# Full_Design.net
KiCad netlist of a schematic drawn in Altium Designer
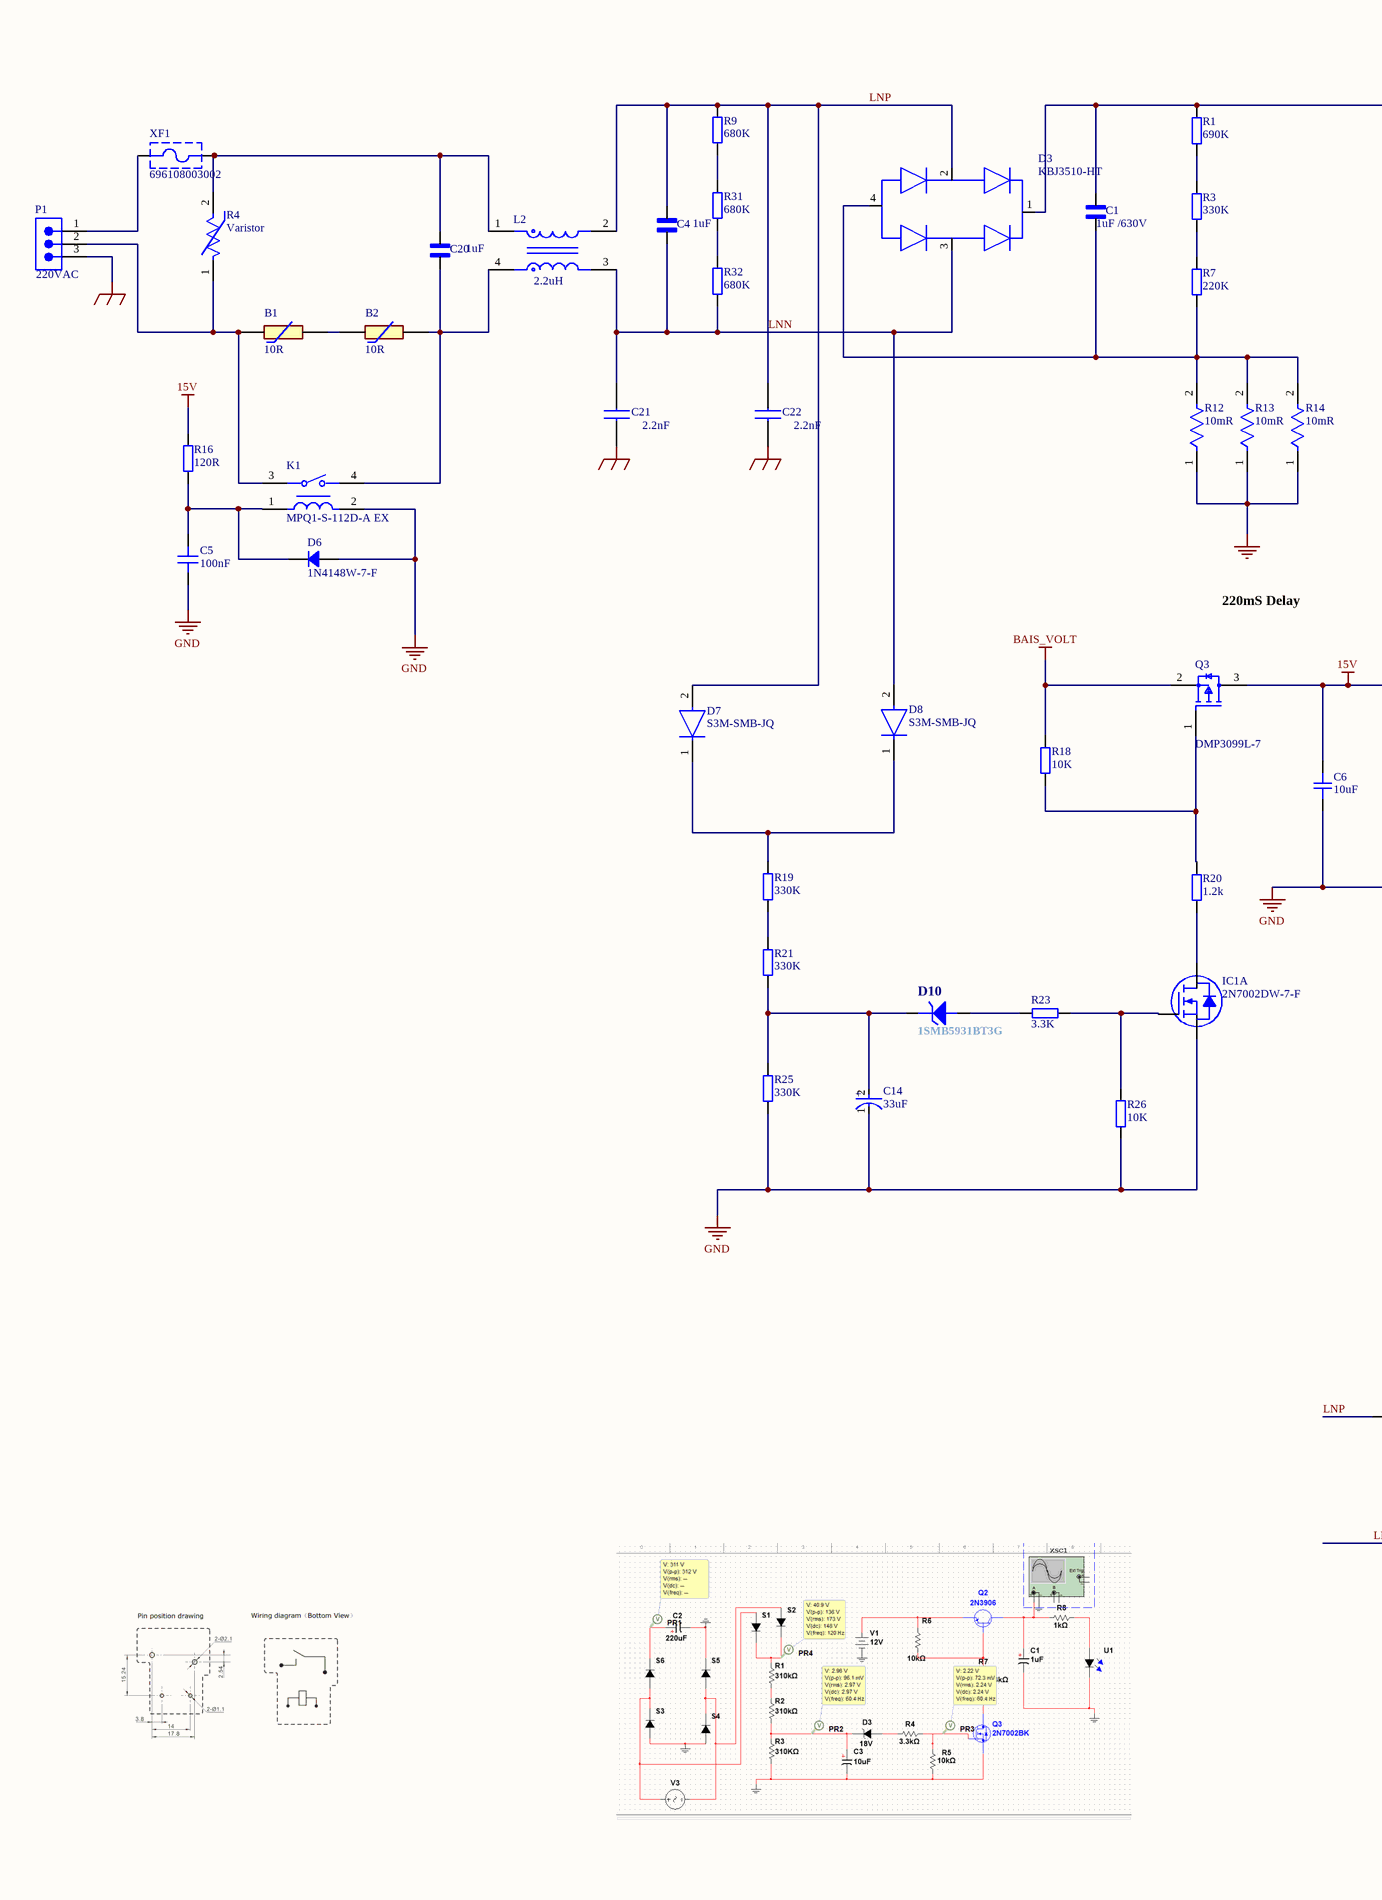
[diagram p0: Full Design.SchDoc, left]
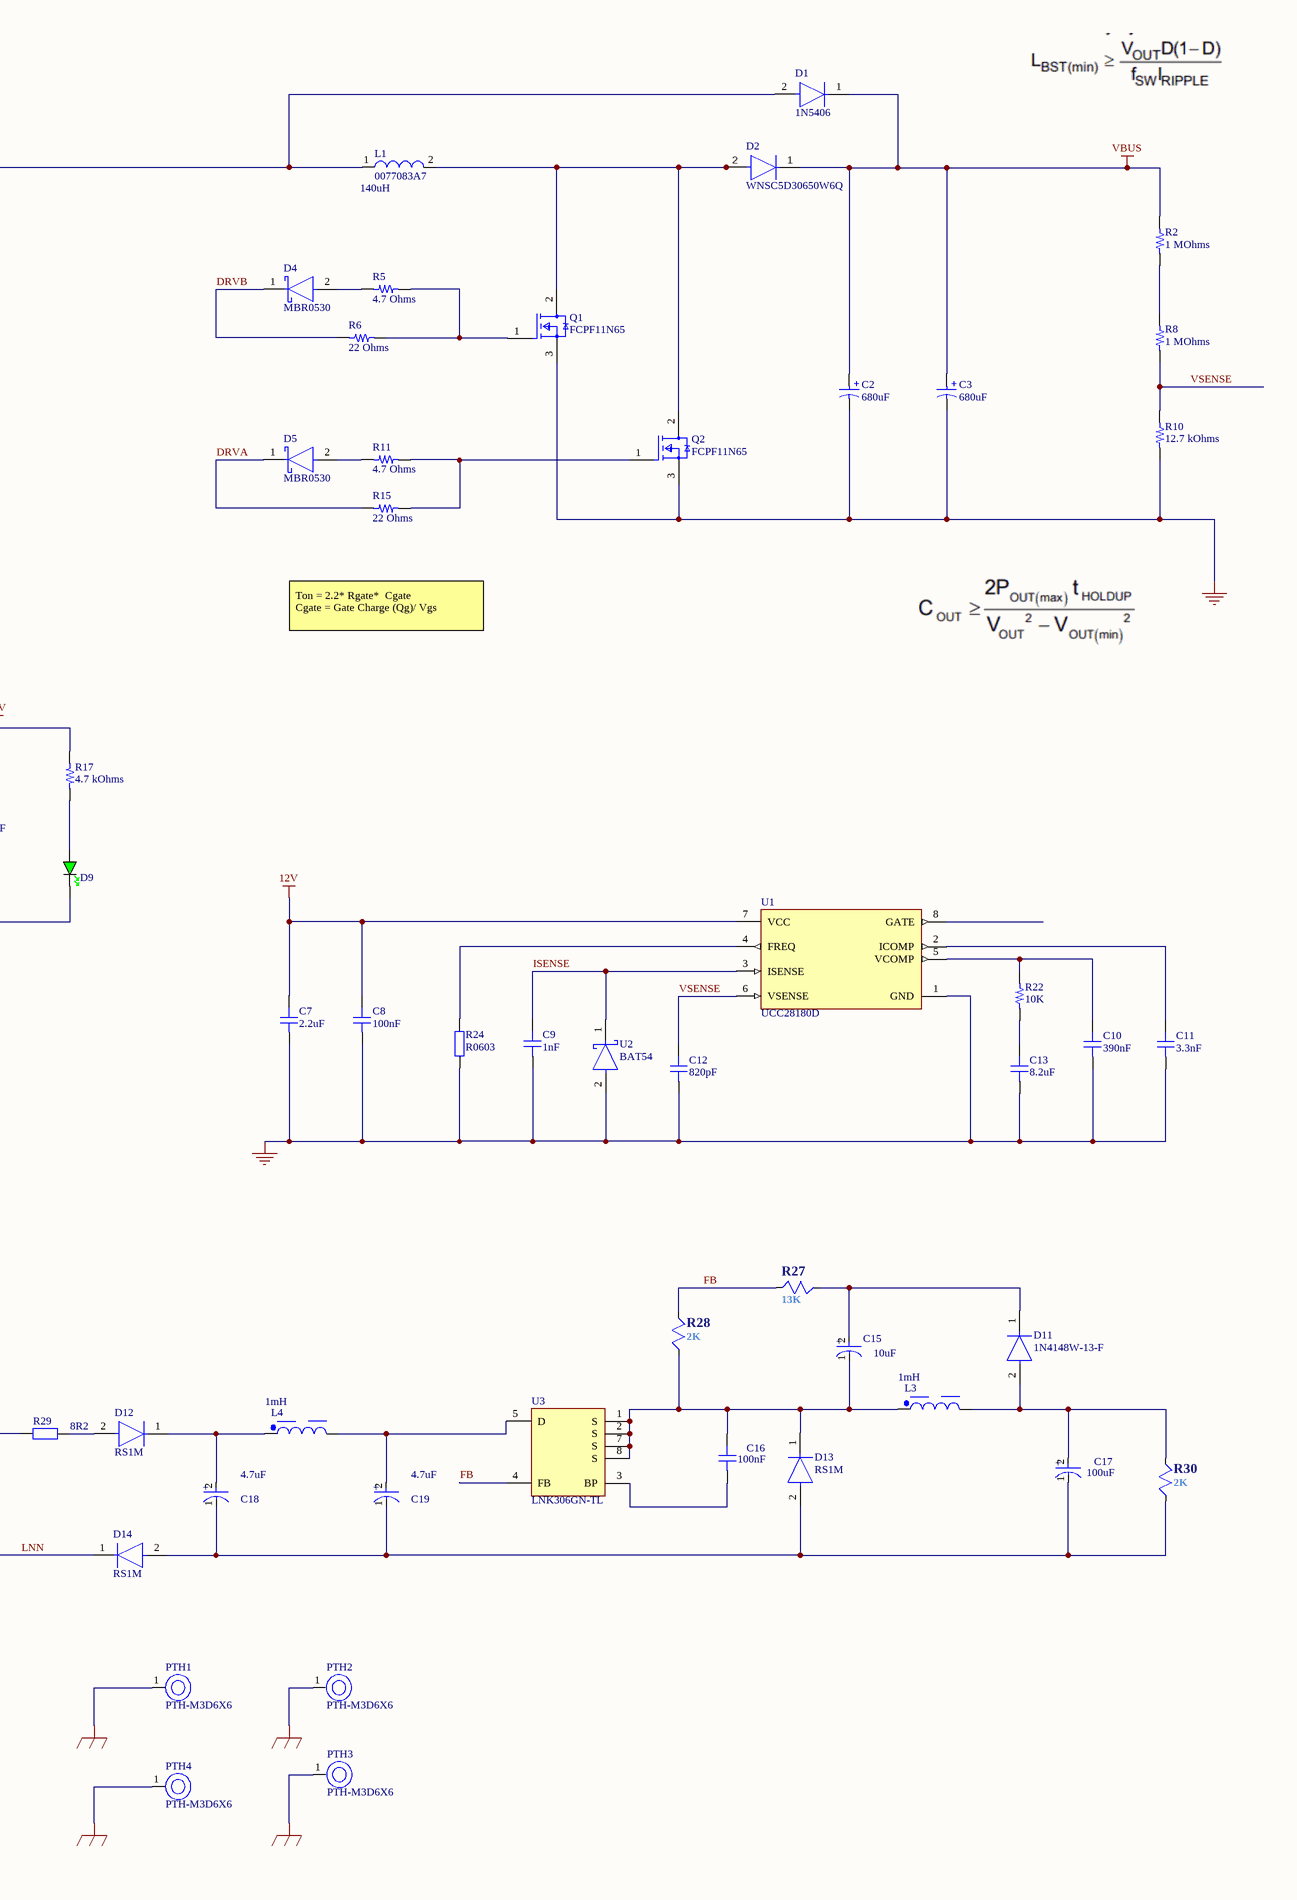
[diagram p1: Full Design.SchDoc, right]

(export (version "E")
  (design (tool "Eeschema 10.0.6"))
  (components
    (comp (ref "B1")
      (value "10R")
      (footprint "B57237S0100M051")
      (description "NTC Inrush Current Limiters, Resistance (at 25)=10, Maximum Current=3.7A")
      (fields
        (field (name "MOUSER PART NUMBER") "871-B57237S0100M051")
        (field (name "MANUFACTURER_PART_NUMBER") "B57237S0100M051")
      )
      (libsource (lib "Görev Yükü's Libary") (part "B57237S0100M051"))
    )
    (comp (ref "B2")
      (value "10R")
      (footprint "B57237S0100M051")
      (description "NTC Inrush Current Limiters, Resistance (at 25)=10, Maximum Current=3.7A")
      (fields
        (field (name "MOUSER PART NUMBER") "871-B57237S0100M051")
        (field (name "MANUFACTURER_PART_NUMBER") "B57237S0100M051")
      )
      (libsource (lib "Görev Yükü's Libary") (part "B57237S0100M051"))
    )
    (comp (ref "C1")
      (value "1uF /630V")
      (footprint "CAPRR2750W80L3150T1100H1900")
      (description "CAP FILM 1UF 10% 630VDC RADIAL")
      (fields (field (name "MF") "EPCOS - TDK Electronics") (field (name "MP") "B32924C3105K000"))
      (libsource (lib "Görev Yükü's Libary") (part "CAP_B32924C3105K189"))
    )
    (comp (ref "C2")
      (value "680uF")
      (footprint "WCAP-AI3H_D35H55")
      (description "CAP.EL.680uF ±20%  450V 2.2A 5000 Hrs @ 105°C")
      (fields (field (name "TOLERANCE") "20%"))
      (libsource (lib "Altium Content Vault") (part "Capacitor_Polarized"))
    )
    (comp (ref "C3")
      (value "680uF")
      (footprint "WCAP-AI3H_D35H55")
      (description "CAP.EL.680uF ±20%  450V 2.2A 5000 Hrs @ 105°C")
      (fields (field (name "TOLERANCE") "20%"))
      (libsource (lib "Altium Content Vault") (part "Capacitor_Polarized"))
    )
    (comp (ref "C4")
      (value "1uF")
      (footprint "CAPRR2750W80L3150T1100H1900")
      (description "CAP FILM 1UF 10% 630VDC RADIAL")
      (fields
        (field (name "MF") "{'manufacturer': u'EPCOS - TDK Electronics'}")
        (field (name "MP") "B32924C3105K000")
      )
      (libsource (lib "Görev Yükü's Libary") (part "CAP_B32924C3105K189"))
    )
    (comp (ref "C5")
      (value "100nF")
      (footprint "CAP 0603_1608")
      (description "CAP CER 1UF 16V X7R 0603")
      (fields (field (name "PART NUMBER") "C0603C105K4RACAUTO") (field (name "MANUFACTURER") "KEMET"))
      (libsource (lib "Celestial Altium Library - altium_library") (part "Capacitor"))
    )
    (comp (ref "C6")
      (value "10uF")
      (footprint "CAP_0805")
      (description "Capacitor SMD 0805")
      (libsource (lib "Phil-lab") (part "CAP_0805"))
    )
    (comp (ref "C7")
      (value "2.2uF")
      (footprint "CAP_0805")
      (description "2.2uF 50V")
      (libsource (lib "Phil-lab") (part "CAP_0805"))
    )
    (comp (ref "C8")
      (value "100nF")
      (footprint "CAP_0805")
      (description "Capacitor SMD 0805")
      (libsource (lib "Phil-lab") (part "CAP_0805"))
    )
    (comp (ref "C9")
      (value "1nF")
      (footprint "CAP_0805")
      (description "Capacitor SMD 0805")
      (libsource (lib "Phil-lab") (part "CAP_0805"))
    )
    (comp (ref "C10")
      (value "390nF")
      (footprint "CAP_0805")
      (description "Capacitor SMD 0805")
      (libsource (lib "Phil-lab") (part "CAP_0805"))
    )
    (comp (ref "C11")
      (value "3.3nF")
      (footprint "CAP_0805")
      (description "Capacitor SMD 0805")
      (libsource (lib "Phil-lab") (part "CAP_0805"))
    )
    (comp (ref "C12")
      (value "820pF")
      (footprint "CAP_0805")
      (description "Capacitor SMD 0805")
      (libsource (lib "Phil-lab") (part "CAP_0805"))
    )
    (comp (ref "C13")
      (value "8.2uF")
      (footprint "CAP_0805")
      (description "Capacitor SMD 0805")
      (libsource (lib "Phil-lab") (part "CAP_0805"))
    )
    (comp (ref "C14")
      (value "33uF")
      (footprint "FP-FKE-MFG")
      (fields (field (name "VOLTAGE") "50V") (field (name "TOLERANCE") "20%"))
      (libsource (lib "Altium Content Vault") (part "203bc49f2ac43e59fd269a8c329ed05"))
    )
    (comp (ref "C15")
      (value "SC1V106M05005VR")
      (footprint "FP-FKC-MFG")
      (description "CAP.EL.10uF 35V 5x5.3 85C SMD SAMWHA")
      (fields
        (field (name "TOLERANCE") "20%")
        (field (name "VOLTAGE") "35V")
        (field (name "CAPACITANCE") "10uF")
      )
      (libsource (lib "Altium Content Vault") (part "a00bbbee19879c290e62620ae7e47b1"))
    )
    (comp (ref "C16")
      (value "C1210C104KCRACTU")
      (footprint "CAP_1210")
      (description "Capacitor SMD 1210")
      (fields (field (name "MANUFACTURER") "KEMET") (field (name "CAPACITANCE") "100nF"))
      (libsource (lib "Phil-lab") (part "CAP_1210"))
    )
    (comp (ref "C17")
      (value "CKL025M101F10PKKKV00A")
      (footprint "FP-SEV8X10_5-MFG")
      (description "CAP.EL.100uF 25V 8x10 105C 5000H AEC-Q200 SMT")
      (fields (field (name "CAPACITANCE") "100uF") (field (name "TOLERANCE") "20%"))
      (libsource (lib "Altium Content Vault") (part "203bc49f2ac43e59fd269a8c329ed05"))
    )
    (comp (ref "C18")
      (value "PKLH-400V4R7MG125-T/A5.0")
      (footprint "FP-RAD-TH-D_10_0_5-L_12_5-MFG")
      (description "CAP.EL.4u7 400V 10X12.5 5MM %20 105C LOW IMP")
      (fields (field (name "TOLERANCE") "20%") (field (name "CAPACITANCE") "4.7uF"))
      (libsource (lib "Altium Content Vault") (part "203bc49f2ac43e59fd269a8c329ed05"))
    )
    (comp (ref "C19")
      (value "PKLH-400V4R7MG125-T/A5.0")
      (footprint "FP-RAD-TH-D_10_0_5-L_12_5-MFG")
      (description "CAP.EL.4u7 400V 10X12.5 5MM %20 105C LOW IMP")
      (fields (field (name "TOLERANCE") "20%") (field (name "CAPACITANCE") "4.7uF"))
      (libsource (lib "Altium Content Vault") (part "203bc49f2ac43e59fd269a8c329ed05"))
    )
    (comp (ref "C20")
      (value "1uF")
      (footprint "CAPRR2750W80L3150T1100H1900")
      (description "CAP FILM 1UF 10% 630VDC RADIAL")
      (fields
        (field (name "MF") "{'manufacturer': u'EPCOS - TDK Electronics'}")
        (field (name "MP") "B32924C3105K000")
      )
      (libsource (lib "Görev Yükü's Libary") (part "CAP_B32924C3105K189"))
    )
    (comp (ref "C21")
      (value "2.2nF")
      (footprint "WYO222MCMBRAKR")
      (description "2200 pF +/-20% 440VAC Ceramic Capacitor Y5U (E) Radial, Disc")
      (fields
        (field (name "MANUFACTURER_PART_NUMBER") "WYO222MCMBRAKR")
        (field (name "MOUSER PART NUMBER") "75-WYO222MCMBRAKR")
      )
      (libsource (lib "Görev Yükü's Libary") (part "WYO222MCMBRAKR"))
    )
    (comp (ref "C22")
      (value "2.2nF")
      (footprint "WYO222MCMBRAKR")
      (description "2200 pF +/-20% 440VAC Ceramic Capacitor Y5U (E) Radial, Disc")
      (fields
        (field (name "MANUFACTURER_PART_NUMBER") "WYO222MCMBRAKR")
        (field (name "MOUSER PART NUMBER") "75-WYO222MCMBRAKR")
      )
      (libsource (lib "Görev Yükü's Libary") (part "WYO222MCMBRAKR"))
    )
    (comp (ref "D1")
      (value "1N5406")
      (footprint "FP-1N5406-E3-54-MFG")
      (description "DIODE GEN PURP 600V 3A DO201AD")
      (libsource (lib "Altium Content Vault") (part "d7152d700b627762746794eb795d46e"))
    )
    (comp (ref "D2")
      (value "WNSC5D30650W6Q")
      (footprint "Diode")
      (description "DIODE SIL.CARB.SCHOTTKY 30A 650V TO247F-2L THT")
      (libsource (lib "Görev Yükü's Libary") (part "Diode,"))
    )
    (comp (ref "D3")
      (value "KBJ3510-HT")
      (footprint "DIOB_GBJ2510-F")
      (description "DIODE BRIDGE 35A 1000V 1PH KBJ THT")
      (libsource (lib "Görev Yükü's Libary") (part "KBJ3510-HT"))
    )
    (comp (ref "D4")
      (value "MBR0530")
      (footprint "FP-425-04-MFG")
      (description "DIODE SCHOTTKY 30V 500MA SOD123")
      (libsource (lib "Altium Content Vault") (part "1d6ec82d83fb6aee721767c19dac4b9"))
    )
    (comp (ref "D5")
      (value "MBR0530")
      (footprint "FP-425-04-MFG")
      (description "DIODE SCHOTTKY 30V 500MA SOD123")
      (libsource (lib "Altium Content Vault") (part "1d6ec82d83fb6aee721767c19dac4b9"))
    )
    (comp (ref "D6")
      (value "1N4148W-7-F")
      (footprint "SOD-123")
      (description "DIODE GEN PURP 100V 300MA SOD123")
      (fields (field (name "MANUFACTURER") "Diodes Incorporated"))
      (libsource (lib "Celestial Altium Library - altium_library") (part "Diode"))
    )
    (comp (ref "D7")
      (value "S3M-SMB-JQ")
      (footprint "FP-95401-MFG")
      (description "DIODE STAND. Single 3A 1000V SMT DO214AA")
      (libsource (lib "Altium Content Vault") (part "d7152d700b627762746794eb795d46e"))
    )
    (comp (ref "D8")
      (value "S3M-SMB-JQ")
      (footprint "FP-95401-MFG")
      (description "-DIODE STAND. Single 3A 1000V SMT DO214AA")
      (libsource (lib "Altium Content Vault") (part "d7152d700b627762746794eb795d46e"))
    )
    (comp (ref "D9")
      (value "GREEN")
      (footprint "LED_0603_GREEN")
      (description "LED 0603 GREEN SMD")
      (libsource (lib "Phil-lab") (part "LED_0603_GREEN"))
    )
    (comp (ref "D10")
      (value "1SMB5931BT3G")
      (footprint "SMB")
      (description "DIODE ZENER 3W 18V ±5% DO214AA (SMB) SMT")
      (libsource (lib "WG_MainBoard_NV1") (part "ZENER-1_1"))
    )
    (comp (ref "D11")
      (value "1N4148W-13-F")
      (footprint "FP-SOD123-MFG")
      (description "DIODE GEN PURP 100V 150MA SOD123")
      (fields
        (field (name "OCTOPART") "https://octopart.com/1n4148w-13-f-diodes+inc.-2359612")
        (field (name "MANUFACTURER") "Diodes Inc.")
      )
      (libsource (lib "Altium Content Vault") (part "d7152d700b627762746794eb795d46e"))
    )
    (comp (ref "D12")
      (value "RS1M")
      (footprint "FP-403AE-MFG")
      (description "DIODE GEN PURP 1KV 1A SMA")
      (fields
        (field (name "OCTOPART") "https://octopart.com/rs1m-on+semiconductor-84331238")
        (field (name "MANUFACTURER") "ON Semiconductor")
      )
      (libsource (lib "Altium Content Vault") (part "d7152d700b627762746794eb795d46e"))
    )
    (comp (ref "D13")
      (value "RS1M")
      (footprint "FP-403AE-MFG")
      (description "DIODE GEN PURP 1KV 1A SMA")
      (fields
        (field (name "OCTOPART") "https://octopart.com/rs1m-on+semiconductor-84331238")
        (field (name "MANUFACTURER") "ON Semiconductor")
      )
      (libsource (lib "Altium Content Vault") (part "d7152d700b627762746794eb795d46e"))
    )
    (comp (ref "D14")
      (value "RS1M")
      (footprint "FP-403AE-MFG")
      (description "DIODE GEN PURP 1KV 1A SMA")
      (fields
        (field (name "OCTOPART") "https://octopart.com/rs1m-on+semiconductor-84331238")
        (field (name "MANUFACTURER") "ON Semiconductor")
      )
      (libsource (lib "Altium Content Vault") (part "d7152d700b627762746794eb795d46e"))
    )
    (comp (ref "IC1")
      (value "2N7002DW-7-F")
      (footprint "DIODES SOT-363")
      (description "MOSFET 2N-CH 60V 0.23A SOT-363")
      (fields (field (name "MANUFACTURER") "Diodes Incorporated"))
      (libsource (lib "Celestial Altium Library - altium_library") (part "INFINEON DUAL MOSFET N-CH SOT363"))
    )
    (comp (ref "K1")
      (value "MPQ1-S-112D-A EX")
      (footprint "MPQ1-S-112D-A EX")
      (description "RELAY POWER 30A 12VDC FormA PCB EXPLOSION PROOF")
      (libsource (lib "Schematics") (part "RELAY_MPQ1-S-112D-A EX"))
    )
    (comp (ref "L1")
      (value "0077083A7")
      (footprint "0077083A7")
      (fields (field (name "INDUCTANCE") "140uH"))
      (libsource (lib "Görev Yükü's Libary") (part "0077083A7"))
    )
    (comp (ref "L2")
      (value "2.2uH")
      (footprint "FP-PLA10A-PLH10A-MFG")
      (description "Common Mode Choke Dual 20mH 0.5A 1.8Ω DCR Thru-Hole Bulk")
      (libsource (lib "Altium Content Vault") (part "48057101139d7a9ca9ebeb60f9e3dee"))
    )
    (comp (ref "L3")
      (value "FPI0705-102K(W0.15)")
      (footprint "WE-PD2_1054")
      (description "INDUCTOR POWER 1mH 7.8X7.0X5.0MM SMD")
      (fields (field (name "TOLERANCE") "10%") (field (name "INDUCTANCE") "1mH"))
      (libsource (lib "Altium Content Vault") (part "Inductor - 2"))
    )
    (comp (ref "L4")
      (value "FPI0705-102K(W0.15)")
      (footprint "WE-PD2_1054")
      (description "INDUCTOR POWER 1mH 7.8X7.0X5.0MM SMD")
      (fields (field (name "TOLERANCE") "10%") (field (name "INDUCTANCE") "1mH"))
      (libsource (lib "Altium Content Vault") (part "Inductor - 2"))
    )
    (comp (ref "P1")
      (value "220VAC")
      (footprint "691311700003")
      (fields (field (name "VOLTAGE") "300V"))
      (libsource (lib "Altium Content Vault") (part "TBL - 1R - 03P - Male"))
    )
    (comp (ref "PTH1")
      (value "PTH-M3D6X6")
      (footprint "PH3.2")
      (libsource (lib "Components") (part "PTH_S1"))
    )
    (comp (ref "PTH2")
      (value "PTH-M3D6X6")
      (footprint "PH3.2")
      (libsource (lib "Components") (part "PTH_S1"))
    )
    (comp (ref "PTH3")
      (value "PTH-M3D6X6")
      (footprint "PH3.2")
      (libsource (lib "Components") (part "PTH_S1"))
    )
    (comp (ref "PTH4")
      (value "PTH-M3D6X6")
      (footprint "PH3.2")
      (libsource (lib "Components") (part "PTH_S1"))
    )
    (comp (ref "Q1")
      (value "FCPF11N65")
      (footprint "FP-TO-220F-MFG")
      (description "FCPF11N65 Res Thick Film 1210 13.7 Ohm 1% 1/2W 100ppm/C Molded SMD Embossed Carrier T/R")
      (libsource (lib "Altium Content Vault") (part "277670f45256a45703965f138927d09"))
    )
    (comp (ref "Q2")
      (value "FCPF11N65")
      (footprint "FP-TO-220F-MFG")
      (description "FCPF11N65 Res Thick Film 1210 13.7 Ohm 1% 1/2W 100ppm/C Molded SMD Embossed Carrier T/R")
      (libsource (lib "Altium Content Vault") (part "277670f45256a45703965f138927d09"))
    )
    (comp (ref "Q3")
      (value "DMP3099L-7")
      (footprint "FP-SOT23-IPC_B")
      (description "MOSFET P-CH 30V SOT23")
      (libsource (lib "Altium Content Vault") (part "d876440acba04c58a9f817a20952145"))
    )
    (comp (ref "R1")
      (value "690K")
      (footprint "RES_0603")
      (description "Resistor SMD 0603")
      (libsource (lib "Phil-lab") (part "RES_0603"))
    )
    (comp (ref "R2")
      (value "1 MOhms")
      (footprint "YAGEO RES 0402_1005")
      (description "RES 1 MOHM 1% 1/16W 0402")
      (fields (field (name "PART NUMBER") "AC0402FR-131ML") (field (name "MANUFACTURER") "Yageo"))
      (libsource (lib "Celestial Altium Library - altium_library") (part "Resistor"))
    )
    (comp (ref "R3")
      (value "330K")
      (footprint "RES_0603")
      (description "Resistor SMD 0603")
      (libsource (lib "Phil-lab") (part "RES_0603"))
    )
    (comp (ref "R4")
      (value "Varistor")
      (footprint "FP-B72214S0301K101-0")
      (description "VARISTOR 470V 4.5KA DISC 14MM")
      (fields (field (name "TOLERANCE") "10%"))
      (libsource (lib "Altium Content Vault") (part "78a88060d5b7b043d6e48adc4284376"))
    )
    (comp (ref "R5")
      (value "4.7 Ohms")
      (footprint "RES 0603_1608")
      (description "RES SMD 4.7 OHM 5% 1/10W 0603")
      (fields (field (name "PART NUMBER") "CR0603-J/-4R7ELF") (field (name "MANUFACTURER") "Bourns Inc."))
      (libsource (lib "Celestial Altium Library - altium_library") (part "Resistor"))
    )
    (comp (ref "R6")
      (value "22 Ohms")
      (footprint "RES 0603_1608")
      (description "RES SMD 22 OHM 5% 1/10W 0603")
      (fields (field (name "PART NUMBER") "CR0603-JW-220ELF") (field (name "MANUFACTURER") "Bourns Inc."))
      (libsource (lib "Celestial Altium Library - altium_library") (part "Resistor"))
    )
    (comp (ref "R7")
      (value "220K")
      (footprint "RES_0603")
      (description "Resistor SMD 0603")
      (libsource (lib "Phil-lab") (part "RES_0603"))
    )
    (comp (ref "R8")
      (value "1 MOhms")
      (footprint "YAGEO RES 0402_1005")
      (description "RES 1 MOHM 1% 1/16W 0402")
      (fields (field (name "PART NUMBER") "AC0402FR-131ML") (field (name "MANUFACTURER") "Yageo"))
      (libsource (lib "Celestial Altium Library - altium_library") (part "Resistor"))
    )
    (comp (ref "R9")
      (value "680K")
      (footprint "RES_0603")
      (description "Resistor SMD 0603")
      (libsource (lib "Phil-lab") (part "RES_0603"))
    )
    (comp (ref "R10")
      (value "12.7 kOhms")
      (footprint "RES 0402_1005")
      (description "RES 12.7K OHM 1% 1/16W 0402")
      (fields
        (field (name "PART NUMBER") "RMCF0402FT12K7")
        (field (name "MANUFACTURER") "Stackpole Electronics Inc")
      )
      (libsource (lib "Celestial Altium Library - altium_library") (part "Resistor"))
    )
    (comp (ref "R11")
      (value "4.7 Ohms")
      (footprint "RES 0603_1608")
      (description "RES SMD 4.7 OHM 5% 1/10W 0603")
      (fields (field (name "PART NUMBER") "CR0603-J/-4R7ELF") (field (name "MANUFACTURER") "Bourns Inc."))
      (libsource (lib "Celestial Altium Library - altium_library") (part "Resistor"))
    )
    (comp (ref "R12")
      (value "10mR")
      (footprint "FP-CSRN2512-IPC_A")
      (description "PE2512FKE7W0R01L  2512 10m Ohms 1% 2W 50PPM")
      (fields (field (name "TOLERANCE") "1%"))
      (libsource (lib "Altium Content Vault") (part "1029c3af85768c4190bb7ad29bc67b5"))
    )
    (comp (ref "R13")
      (value "10mR")
      (footprint "FP-CSRN2512-IPC_A")
      (description "PE2512FKE7W0R01L  2512 10m Ohms 1% 2W 50PPM")
      (fields (field (name "TOLERANCE") "1%"))
      (libsource (lib "Altium Content Vault") (part "1029c3af85768c4190bb7ad29bc67b5"))
    )
    (comp (ref "R14")
      (value "10mR")
      (footprint "FP-CSRN2512-IPC_A")
      (description "PE2512FKE7W0R01L 2512 10m Ohms 1% 2W 50PPM")
      (fields (field (name "TOLERANCE") "1%"))
      (libsource (lib "Altium Content Vault") (part "1029c3af85768c4190bb7ad29bc67b5"))
    )
    (comp (ref "R15")
      (value "22 Ohms")
      (footprint "RES 0603_1608")
      (description "RES SMD 22 OHM 5% 1/10W 0603")
      (fields (field (name "PART NUMBER") "CR0603-JW-220ELF") (field (name "MANUFACTURER") "Bourns Inc."))
      (libsource (lib "Celestial Altium Library - altium_library") (part "Resistor"))
    )
    (comp (ref "R16")
      (value "120R")
      (footprint "RES_0603")
      (description "Resistor SMD 0603")
      (libsource (lib "Phil-lab") (part "RES_0603"))
    )
    (comp (ref "R17")
      (value "4.7 kOhms")
      (footprint "RES 0603_1608")
      (description "RES SMD 4.7K OHM 5% 1/10W 0603")
      (fields (field (name "PART NUMBER") "CR0603-JW-472ELF") (field (name "MANUFACTURER") "Bourns Inc."))
      (libsource (lib "Celestial Altium Library - altium_library") (part "Resistor"))
    )
    (comp (ref "R18")
      (value "10K")
      (footprint "RES_0603")
      (description "Resistor SMD 0603")
      (libsource (lib "Phil-lab") (part "RES_0603"))
    )
    (comp (ref "R19")
      (value "330K")
      (footprint "RES_0603")
      (description "Resistor SMD 0603")
      (libsource (lib "Phil-lab") (part "RES_0603"))
    )
    (comp (ref "R20")
      (value "1.2k")
      (footprint "RES_0603")
      (description "Resistor SMD 0603")
      (libsource (lib "Phil-lab") (part "RES_0603"))
    )
    (comp (ref "R21")
      (value "330K")
      (footprint "RES_0603")
      (description "Resistor SMD 0603")
      (libsource (lib "Phil-lab") (part "RES_0603"))
    )
    (comp (ref "R22")
      (value "10K")
      (footprint "RES 0402_1005")
      (description "RES 22.9K OHM 0.1% 1/16W 0402")
      (fields (field (name "PART NUMBER") "TNPW040222K9BEED") (field (name "MANUFACTURER") "Vishay Dale"))
      (libsource (lib "Celestial Altium Library - altium_library") (part "Resistor"))
    )
    (comp (ref "R23")
      (value "3.3K")
      (footprint "RES_0603")
      (description "Resistor SMD 0603")
      (libsource (lib "Phil-lab") (part "RES_0603"))
    )
    (comp (ref "R24")
      (value "R0603")
      (footprint "RES_0603")
      (description "Resistor SMD 0603")
      (libsource (lib "Phil-lab") (part "RES_0603"))
    )
    (comp (ref "R25")
      (value "330K")
      (footprint "RES_0603")
      (description "Resistor SMD 0603")
      (libsource (lib "Phil-lab") (part "RES_0603"))
    )
    (comp (ref "R26")
      (value "10K")
      (footprint "RES_0603")
      (description "Resistor SMD 0603")
      (libsource (lib "Phil-lab") (part "RES_0603"))
    )
    (comp (ref "R27")
      (value "13K")
      (footprint "RESC1608N")
      (description "RES.(1608) 0603 13K Ohms 1% 1/10W-S 100PPM")
      (fields (field (name "Comment") "0603SAF1302T5E"))
      (libsource (lib "*") (part "RES"))
    )
    (comp (ref "R28")
      (value "2K")
      (footprint "RESC1608N")
      (description "RES.(1608) 0603 2K Ohms 1% 1/5W")
      (fields (field (name "Comment") "HP03W5F2001T5E"))
      (libsource (lib "*") (part "RES"))
    )
    (comp (ref "R29")
      (value "8R2")
      (footprint "AXIAL-0.4")
      (description "Resistor")
      (fields (field (name "Comment") "FKN2WSJT-73-10R") (field (name "PUBLISHER") "Altium Limited"))
      (libsource (lib "Miscellaneous Devices") (part "Res2"))
    )
    (comp (ref "R30")
      (value "2K")
      (footprint "RESC1608N")
      (description "RES.(1608) 0603 2K Ohms 1% 1/5W")
      (fields (field (name "Comment") "HP03W5F2001T5E"))
      (libsource (lib "*") (part "RES"))
    )
    (comp (ref "R31")
      (value "680K")
      (footprint "RES_0603")
      (description "Resistor SMD 0603")
      (libsource (lib "Phil-lab") (part "RES_0603"))
    )
    (comp (ref "R32")
      (value "680K")
      (footprint "RES_0603")
      (description "Resistor SMD 0603")
      (libsource (lib "Phil-lab") (part "RES_0603"))
    )
    (comp (ref "U1")
      (value "UCC28180D")
      (footprint "FP-D0008A-MFG")
      (description "IC PFC CTRLR AVERAGE CURR 8SOIC")
      (fields
        (field (name "OCTOPART") "https://octopart.com/ucc28180d-texas+instruments-31566950")
        (field (name "MANUFACTURER") "Texas Instruments")
      )
      (libsource (lib "Altium Content Vault") (part "c95dd6f63eea92a43b6a1c8dc0b98c9"))
    )
    (comp (ref "U2")
      (value "BAT54")
      (footprint "FP-SOD323-MFG")
      (description "DIODE SCHOTTKY 40V 300MA SOD323")
      (fields
        (field (name "MANUFACTURER PART NUMBER") "BAT54JFILM")
        (field (name "OCTOPART") "https://octopart.com/bat54jfilm-stmicroelectronics-326073")
      )
      (libsource (lib "Altium Content Vault") (part "1d6ec82d83fb6aee721767c19dac4b9"))
    )
    (comp (ref "U3")
      (value "LNK306GN-TL")
      (footprint "PI-SMD-8B-7_V")
      (fields (field (name "MANUFACTURER") "Power Integrations"))
      (libsource (lib "Altium Content Vault") (part "PI-LNK30X-G_P-7"))
    )
    (comp (ref "XF1")
      (value "696108003002")
      (footprint "696108003002")
      (libsource (lib "Altium Content Vault") (part "Fuse Holder"))
    )
  )
  (nets
    (net (code "1") (name "/DRVA") (class "Default")
      (node (ref "D5") (pin "1") (pinfunction "C_1") (pintype "passive"))
      (node (ref "R15") (pin "1") (pinfunction "1_1") (pintype "passive"))
    )
    (net (code "2") (name "/DRVB") (class "Default")
      (node (ref "D4") (pin "1") (pinfunction "C_1") (pintype "passive"))
      (node (ref "R6") (pin "1") (pinfunction "1_1") (pintype "passive"))
    )
    (net (code "3") (name "/FB") (class "Default")
      (node (ref "R27") (pin "2") (pinfunction "2_2") (pintype "passive"))
      (node (ref "R28") (pin "1") (pinfunction "1_1") (pintype "passive"))
      (node (ref "U3") (pin "4") (pinfunction "FB_4") (pintype "passive"))
    )
    (net (code "4") (name "/ISENSE") (class "Default")
      (node (ref "C9") (pin "2") (pinfunction "2_2") (pintype "passive"))
      (node (ref "U1") (pin "3") (pinfunction "ISENSE_3") (pintype "input"))
      (node (ref "U2") (pin "1") (pinfunction "C_1") (pintype "passive"))
    )
    (net (code "5") (name "/LNN") (class "Default")
      (node (ref "C21") (pin "2") (pinfunction "2_2") (pintype "passive"))
      (node (ref "C22") (pin "2") (pinfunction "2_2") (pintype "passive"))
      (node (ref "C4") (pin "1") (pinfunction "1_1") (pintype "passive"))
      (node (ref "C4") (pin "2") (pinfunction "2_2") (pintype "passive"))
      (node (ref "D14") (pin "1") (pinfunction "C_1") (pintype "passive"))
      (node (ref "D3") (pin "2") (pinfunction "2_2") (pintype "passive"))
      (node (ref "D3") (pin "3") (pinfunction "3_3") (pintype "passive"))
      (node (ref "D7") (pin "2") (pinfunction "A_2") (pintype "passive"))
      (node (ref "D8") (pin "2") (pinfunction "A_2") (pintype "passive"))
      (node (ref "L2") (pin "2") (pinfunction "2_2") (pintype "passive"))
      (node (ref "L2") (pin "3") (pinfunction "3_3") (pintype "passive"))
      (node (ref "R29") (pin "1") (pinfunction "1_1") (pintype "passive"))
      (node (ref "R32") (pin "1") (pinfunction "1_1") (pintype "passive"))
      (node (ref "R9") (pin "2") (pinfunction "2_2") (pintype "passive"))
    )
    (net (code "6") (name "/VSENSE") (class "Default")
      (node (ref "C12") (pin "2") (pinfunction "2_2") (pintype "passive"))
      (node (ref "R10") (pin "1") (pinfunction "1_1") (pintype "passive"))
      (node (ref "R8") (pin "1") (pinfunction "1_1") (pintype "passive"))
      (node (ref "U1") (pin "6") (pinfunction "VSENSE_6") (pintype "input"))
    )
    (net (code "7") (name "12V") (class "Default")
      (node (ref "C7") (pin "2") (pinfunction "2_2") (pintype "passive"))
      (node (ref "C8") (pin "2") (pinfunction "2_2") (pintype "passive"))
      (node (ref "U1") (pin "7") (pinfunction "VCC_7") (pintype "power_in"))
    )
    (net (code "8") (name "15V") (class "Default")
      (node (ref "C6") (pin "1") (pinfunction "1_1") (pintype "passive"))
      (node (ref "Q3") (pin "3") (pinfunction "D_3") (pintype "passive"))
      (node (ref "R16") (pin "2") (pinfunction "2_2") (pintype "passive"))
      (node (ref "R17") (pin "1") (pinfunction "1_1") (pintype "passive"))
    )
    (net (code "9") (name "BAIS_VOLT") (class "Default")
      (node (ref "Q3") (pin "2") (pinfunction "S_2") (pintype "passive"))
      (node (ref "R18") (pin "2") (pinfunction "2_2") (pintype "passive"))
    )
    (net (code "10") (name "EARTH") (class "Default")
      (node (ref "C21") (pin "1") (pinfunction "1_1") (pintype "passive"))
      (node (ref "C22") (pin "1") (pinfunction "1_1") (pintype "passive"))
      (node (ref "P1") (pin "3") (pinfunction "3_3") (pintype "passive"))
      (node (ref "PTH1") (pin "1") (pinfunction "1_1") (pintype "passive"))
      (node (ref "PTH2") (pin "1") (pinfunction "1_1") (pintype "passive"))
      (node (ref "PTH3") (pin "1") (pinfunction "1_1") (pintype "passive"))
      (node (ref "PTH4") (pin "1") (pinfunction "1_1") (pintype "passive"))
    )
    (net (code "11") (name "GND") (class "Default")
      (node (ref "C10") (pin "1") (pinfunction "1_1") (pintype "passive"))
      (node (ref "C11") (pin "1") (pinfunction "1_1") (pintype "passive"))
      (node (ref "C12") (pin "1") (pinfunction "1_1") (pintype "passive"))
      (node (ref "C13") (pin "1") (pinfunction "1_1") (pintype "passive"))
      (node (ref "C14") (pin "1") (pinfunction "C_1") (pintype "passive"))
      (node (ref "C2") (pin "2") (pinfunction "N_2") (pintype "passive"))
      (node (ref "C3") (pin "2") (pinfunction "N_2") (pintype "passive"))
      (node (ref "C5") (pin "1") (pinfunction "1_1") (pintype "passive"))
      (node (ref "C6") (pin "2") (pinfunction "2_2") (pintype "passive"))
      (node (ref "C7") (pin "1") (pinfunction "1_1") (pintype "passive"))
      (node (ref "C8") (pin "1") (pinfunction "1_1") (pintype "passive"))
      (node (ref "C9") (pin "1") (pinfunction "1_1") (pintype "passive"))
      (node (ref "D6") (pin "1") (pinfunction "1_1") (pintype "passive"))
      (node (ref "D9") (pin "K") (pinfunction "K_K") (pintype "passive"))
      (node (ref "IC1") (pin "1") (pinfunction "S1_1") (pintype "passive"))
      (node (ref "K1") (pin "2") (pinfunction "2_2") (pintype "passive"))
      (node (ref "Q1") (pin "3") (pinfunction "S_3") (pintype "passive"))
      (node (ref "Q2") (pin "3") (pinfunction "S_3") (pintype "passive"))
      (node (ref "R10") (pin "2") (pinfunction "2_2") (pintype "passive"))
      (node (ref "R12") (pin "1") (pinfunction "1_1") (pintype "passive"))
      (node (ref "R13") (pin "1") (pinfunction "1_1") (pintype "passive"))
      (node (ref "R14") (pin "1") (pinfunction "1_1") (pintype "passive"))
      (node (ref "R24") (pin "1") (pinfunction "1_1") (pintype "passive"))
      (node (ref "R25") (pin "1") (pinfunction "1_1") (pintype "passive"))
      (node (ref "R26") (pin "1") (pinfunction "1_1") (pintype "passive"))
      (node (ref "U1") (pin "1") (pinfunction "GND_1") (pintype "power_in"))
      (node (ref "U2") (pin "2") (pinfunction "A_2") (pintype "passive"))
    )
    (net (code "12") (name "Net-(B1-Pad1)") (class "Default")
      (node (ref "B1") (pin "1") (pinfunction "1_1") (pintype "passive"))
      (node (ref "K1") (pin "3") (pinfunction "3_3") (pintype "passive"))
      (node (ref "P1") (pin "2") (pinfunction "2_2") (pintype "passive"))
      (node (ref "R4") (pin "1") (pinfunction "1_1") (pintype "passive"))
    )
    (net (code "13") (name "Net-(B1-Pad2)") (class "Default")
      (node (ref "B1") (pin "2") (pinfunction "2_2") (pintype "passive"))
      (node (ref "B2") (pin "1") (pinfunction "1_1") (pintype "passive"))
    )
    (net (code "14") (name "Net-(B2-Pad2)") (class "Default")
      (node (ref "B2") (pin "2") (pinfunction "2_2") (pintype "passive"))
      (node (ref "C20") (pin "1") (pinfunction "1_1") (pintype "passive"))
      (node (ref "K1") (pin "4") (pinfunction "4_4") (pintype "passive"))
      (node (ref "L2") (pin "4") (pinfunction "4_4") (pintype "passive"))
    )
    (net (code "15") (name "Net-(C1-Pad1)") (class "Default")
      (node (ref "C1") (pin "1") (pinfunction "1_1") (pintype "passive"))
      (node (ref "D3") (pin "4") (pinfunction "4_4") (pintype "passive"))
      (node (ref "R12") (pin "2") (pinfunction "2_2") (pintype "passive"))
      (node (ref "R13") (pin "2") (pinfunction "2_2") (pintype "passive"))
      (node (ref "R14") (pin "2") (pinfunction "2_2") (pintype "passive"))
      (node (ref "R7") (pin "1") (pinfunction "1_1") (pintype "passive"))
    )
    (net (code "16") (name "Net-(C5-Pad2)") (class "Default")
      (node (ref "C5") (pin "2") (pinfunction "2_2") (pintype "passive"))
      (node (ref "D6") (pin "2") (pinfunction "2_2") (pintype "passive"))
      (node (ref "K1") (pin "1") (pinfunction "1_1") (pintype "passive"))
      (node (ref "R16") (pin "1") (pinfunction "1_1") (pintype "passive"))
    )
    (net (code "17") (name "Net-(C13-Pad2)") (class "Default")
      (node (ref "C13") (pin "2") (pinfunction "2_2") (pintype "passive"))
      (node (ref "R22") (pin "1") (pinfunction "1_1") (pintype "passive"))
    )
    (net (code "18") (name "Net-(C14-A)") (class "Default")
      (node (ref "C14") (pin "2") (pinfunction "A_2") (pintype "passive"))
      (node (ref "D10") (pin "2") (pinfunction "K_2") (pintype "passive"))
      (node (ref "R21") (pin "1") (pinfunction "1_1") (pintype "passive"))
      (node (ref "R25") (pin "2") (pinfunction "2_2") (pintype "passive"))
    )
    (net (code "19") (name "Net-(C15-A)") (class "Default")
      (node (ref "C15") (pin "2") (pinfunction "A_2") (pintype "passive"))
      (node (ref "D11") (pin "1") (pinfunction "C_1") (pintype "passive"))
      (node (ref "R27") (pin "1") (pinfunction "1_1") (pintype "passive"))
    )
    (net (code "20") (name "Net-(C15-C)") (class "Default")
      (node (ref "C15") (pin "1") (pinfunction "C_1") (pintype "passive"))
      (node (ref "C16") (pin "2") (pinfunction "2_2") (pintype "passive"))
      (node (ref "D13") (pin "1") (pinfunction "C_1") (pintype "passive"))
      (node (ref "L3") (pin "1") (pinfunction "1_1") (pintype "passive"))
      (node (ref "R28") (pin "2") (pinfunction "2_2") (pintype "passive"))
      (node (ref "U3") (pin "1") (pinfunction "S_1") (pintype "passive"))
      (node (ref "U3") (pin "2") (pinfunction "S_2") (pintype "passive"))
      (node (ref "U3") (pin "7") (pinfunction "S_7") (pintype "passive"))
      (node (ref "U3") (pin "8") (pinfunction "S_8") (pintype "passive"))
    )
    (net (code "21") (name "Net-(C17-A)") (class "Default")
      (node (ref "C17") (pin "2") (pinfunction "A_2") (pintype "passive"))
      (node (ref "D11") (pin "2") (pinfunction "A_2") (pintype "passive"))
      (node (ref "L3") (pin "2") (pinfunction "2_2") (pintype "passive"))
      (node (ref "R30") (pin "1") (pinfunction "1_1") (pintype "passive"))
    )
    (net (code "22") (name "Net-(C17-C)") (class "Default")
      (node (ref "C17") (pin "1") (pinfunction "C_1") (pintype "passive"))
      (node (ref "C18") (pin "1") (pinfunction "C_1") (pintype "passive"))
      (node (ref "C19") (pin "1") (pinfunction "C_1") (pintype "passive"))
      (node (ref "D13") (pin "2") (pinfunction "A_2") (pintype "passive"))
      (node (ref "D14") (pin "2") (pinfunction "A_2") (pintype "passive"))
      (node (ref "R30") (pin "2") (pinfunction "2_2") (pintype "passive"))
    )
    (net (code "23") (name "Net-(C18-A)") (class "Default")
      (node (ref "C18") (pin "2") (pinfunction "A_2") (pintype "passive"))
      (node (ref "D12") (pin "1") (pinfunction "C_1") (pintype "passive"))
      (node (ref "L4") (pin "1") (pinfunction "1_1") (pintype "passive"))
    )
    (net (code "24") (name "Net-(C19-A)") (class "Default")
      (node (ref "C19") (pin "2") (pinfunction "A_2") (pintype "passive"))
      (node (ref "L4") (pin "2") (pinfunction "2_2") (pintype "passive"))
      (node (ref "U3") (pin "5") (pinfunction "D_5") (pintype "passive"))
    )
    (net (code "25") (name "Net-(C20-Pad2)") (class "Default")
      (node (ref "C20") (pin "2") (pinfunction "2_2") (pintype "passive"))
      (node (ref "L2") (pin "1") (pinfunction "1_1") (pintype "passive"))
      (node (ref "R4") (pin "2") (pinfunction "2_2") (pintype "passive"))
      (node (ref "XF1") (pin "2") (pinfunction "2_2") (pintype "passive"))
    )
    (net (code "26") (name "Net-(D1-A)") (class "Default")
      (node (ref "C1") (pin "2") (pinfunction "2_2") (pintype "passive"))
      (node (ref "D1") (pin "2") (pinfunction "A_2") (pintype "passive"))
      (node (ref "D3") (pin "1") (pinfunction "1_1") (pintype "passive"))
      (node (ref "L1") (pin "1") (pinfunction "1_1") (pintype "passive"))
      (node (ref "R1") (pin "2") (pinfunction "2_2") (pintype "passive"))
    )
    (net (code "27") (name "Net-(D2-A)") (class "Default")
      (node (ref "D2") (pin "2") (pinfunction "A_2") (pintype "passive"))
      (node (ref "L1") (pin "2") (pinfunction "2_2") (pintype "passive"))
      (node (ref "Q1") (pin "2") (pinfunction "D_2") (pintype "passive"))
      (node (ref "Q2") (pin "2") (pinfunction "D_2") (pintype "passive"))
    )
    (net (code "28") (name "Net-(D4-A)") (class "Default")
      (node (ref "D4") (pin "2") (pinfunction "A_2") (pintype "passive"))
      (node (ref "R5") (pin "2") (pinfunction "2_2") (pintype "passive"))
    )
    (net (code "29") (name "Net-(D5-A)") (class "Default")
      (node (ref "D5") (pin "2") (pinfunction "A_2") (pintype "passive"))
      (node (ref "R11") (pin "2") (pinfunction "2_2") (pintype "passive"))
    )
    (net (code "30") (name "Net-(D7-C)") (class "Default")
      (node (ref "D7") (pin "1") (pinfunction "C_1") (pintype "passive"))
      (node (ref "D8") (pin "1") (pinfunction "C_1") (pintype "passive"))
      (node (ref "R19") (pin "2") (pinfunction "2_2") (pintype "passive"))
    )
    (net (code "31") (name "Net-(D9-PadA)") (class "Default")
      (node (ref "D9") (pin "A") (pinfunction "A_A") (pintype "passive"))
      (node (ref "R17") (pin "2") (pinfunction "2_2") (pintype "passive"))
    )
    (net (code "32") (name "Net-(D12-A)") (class "Default")
      (node (ref "D12") (pin "2") (pinfunction "A_2") (pintype "passive"))
      (node (ref "R29") (pin "2") (pinfunction "2_2") (pintype "passive"))
    )
    (net (code "33") (name "Net-(IC1A-D1)") (class "Default")
      (node (ref "IC1") (pin "6") (pinfunction "D1_6") (pintype "passive"))
      (node (ref "R20") (pin "2") (pinfunction "2_2") (pintype "passive"))
    )
    (net (code "34") (name "Net-(IC1A-G1)") (class "Default")
      (node (ref "IC1") (pin "2") (pinfunction "G1_2") (pintype "passive"))
      (node (ref "R23") (pin "1") (pinfunction "1_1") (pintype "passive"))
      (node (ref "R26") (pin "2") (pinfunction "2_2") (pintype "passive"))
    )
    (net (code "35") (name "Net-(P1-Pad1)") (class "Default")
      (node (ref "P1") (pin "1") (pinfunction "1_1") (pintype "passive"))
      (node (ref "XF1") (pin "1") (pinfunction "1_1") (pintype "passive"))
    )
    (net (code "36") (name "Net-(Q1-G)") (class "Default")
      (node (ref "Q1") (pin "1") (pinfunction "G_1") (pintype "passive"))
      (node (ref "R5") (pin "1") (pinfunction "1_1") (pintype "passive"))
      (node (ref "R6") (pin "2") (pinfunction "2_2") (pintype "passive"))
    )
    (net (code "37") (name "Net-(Q2-G)") (class "Default")
      (node (ref "Q2") (pin "1") (pinfunction "G_1") (pintype "passive"))
      (node (ref "R11") (pin "1") (pinfunction "1_1") (pintype "passive"))
      (node (ref "R15") (pin "2") (pinfunction "2_2") (pintype "passive"))
    )
    (net (code "38") (name "Net-(Q3-G)") (class "Default")
      (node (ref "Q3") (pin "1") (pinfunction "G_1") (pintype "passive"))
      (node (ref "R18") (pin "1") (pinfunction "1_1") (pintype "passive"))
      (node (ref "R20") (pin "1") (pinfunction "1_1") (pintype "passive"))
    )
    (net (code "39") (name "Net-(R1-Pad1)") (class "Default")
      (node (ref "R1") (pin "1") (pinfunction "1_1") (pintype "passive"))
      (node (ref "R3") (pin "2") (pinfunction "2_2") (pintype "passive"))
    )
    (net (code "40") (name "Net-(R2-Pad1)") (class "Default")
      (node (ref "R2") (pin "1") (pinfunction "1_1") (pintype "passive"))
      (node (ref "R8") (pin "2") (pinfunction "2_2") (pintype "passive"))
    )
    (net (code "41") (name "Net-(R3-Pad1)") (class "Default")
      (node (ref "R3") (pin "1") (pinfunction "1_1") (pintype "passive"))
      (node (ref "R7") (pin "2") (pinfunction "2_2") (pintype "passive"))
    )
    (net (code "42") (name "Net-(R19-Pad1)") (class "Default")
      (node (ref "R19") (pin "1") (pinfunction "1_1") (pintype "passive"))
      (node (ref "R21") (pin "2") (pinfunction "2_2") (pintype "passive"))
    )
    (net (code "43") (name "Net-(R31-Pad1)") (class "Default")
      (node (ref "R31") (pin "1") (pinfunction "1_1") (pintype "passive"))
      (node (ref "R32") (pin "2") (pinfunction "2_2") (pintype "passive"))
    )
    (net (code "44") (name "Net-(R31-Pad2)") (class "Default")
      (node (ref "R31") (pin "2") (pinfunction "2_2") (pintype "passive"))
      (node (ref "R9") (pin "1") (pinfunction "1_1") (pintype "passive"))
    )
    (net (code "45") (name "Net-(U1-FREQ)") (class "Default")
      (node (ref "R24") (pin "2") (pinfunction "2_2") (pintype "passive"))
      (node (ref "U1") (pin "4") (pinfunction "FREQ_4") (pintype "output"))
    )
    (net (code "46") (name "Net-(U1-ICOMP)") (class "Default")
      (node (ref "C11") (pin "2") (pinfunction "2_2") (pintype "passive"))
      (node (ref "U1") (pin "2") (pinfunction "ICOMP_2") (pintype "output"))
    )
    (net (code "47") (name "Net-(U1-VCOMP)") (class "Default")
      (node (ref "C10") (pin "2") (pinfunction "2_2") (pintype "passive"))
      (node (ref "R22") (pin "2") (pinfunction "2_2") (pintype "passive"))
      (node (ref "U1") (pin "5") (pinfunction "VCOMP_5") (pintype "output"))
    )
    (net (code "48") (name "Net-(U3-BP)") (class "Default")
      (node (ref "C16") (pin "1") (pinfunction "1_1") (pintype "passive"))
      (node (ref "U3") (pin "3") (pinfunction "BP_3") (pintype "passive"))
    )
    (net (code "49") (name "VBUS") (class "Default")
      (node (ref "C2") (pin "1") (pinfunction "P_1") (pintype "passive"))
      (node (ref "C3") (pin "1") (pinfunction "P_1") (pintype "passive"))
      (node (ref "D1") (pin "1") (pinfunction "C_1") (pintype "passive"))
      (node (ref "D2") (pin "1") (pinfunction "K_1") (pintype "passive"))
      (node (ref "R2") (pin "2") (pinfunction "2_2") (pintype "passive"))
    )
    (net (code "50") (name "unconnected-(D10-A-Pad1)") (class "Default")
      (node (ref "D10") (pin "1") (pinfunction "A_1") (pintype "passive"))
    )
    (net (code "51") (name "unconnected-(R23-Pad2)") (class "Default")
      (node (ref "R23") (pin "2") (pinfunction "2_2") (pintype "passive"))
    )
    (net (code "52") (name "unconnected-(U1-GATE-Pad8)") (class "Default")
      (node (ref "U1") (pin "8") (pinfunction "GATE_8") (pintype "output"))
    )
  )
)
